# QUTMS-BrakeLight-S00-V01.net
KiCad netlist of a schematic drawn in Altium Designer
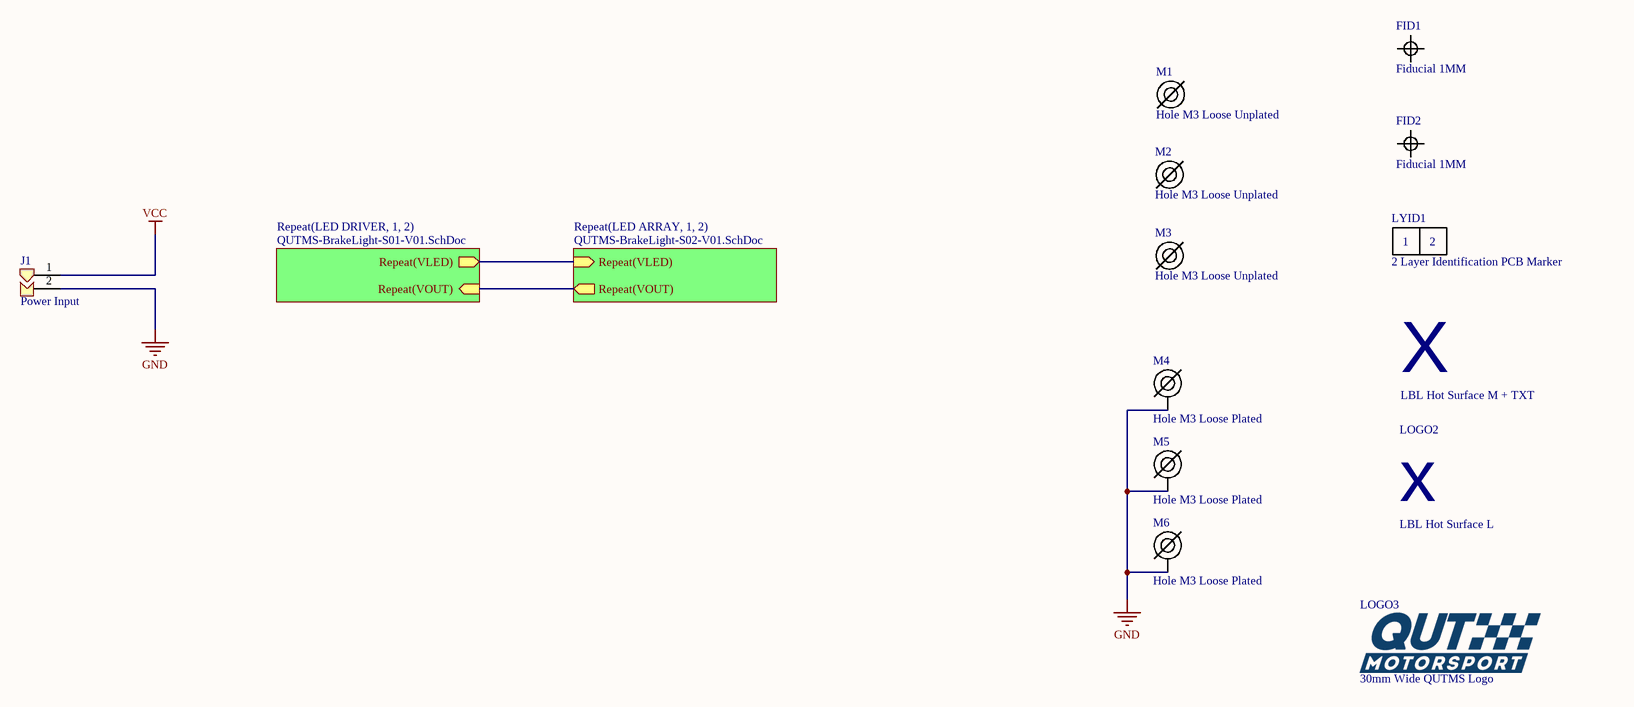
[diagram p0: QUTMS-BrakeLight-S00-V01.SchDoc]

(export (version "E")
  (design (tool "Eeschema 10.0.6"))
  (components
    (comp (ref "FID1")
      (value "Fiducial 1MM")
      (footprint "FIDUCIAL 1MM")
      (libsource (lib "QUTMS_PCBLibrary") (part "Fiducial 1MM"))
    )
    (comp (ref "FID2")
      (value "Fiducial 1MM")
      (footprint "FIDUCIAL 1MM")
      (libsource (lib "QUTMS_PCBLibrary") (part "Fiducial 1MM"))
    )
    (comp (ref "J1")
      (value "Power Input")
      (footprint "Jumper_2Way_Large_Solder_Pad")
      (description "Jumper 2Way Side Large Solderable Pad")
      (libsource (lib "QUTMS_JumperLibrary") (part "Jumper 2Way Side Large Solder Pad"))
    )
    (comp (ref "LOGO1")
      (value "LBL Hot Surface M + TXT")
      (footprint "LBL HOT MEDIUM TXT")
      (libsource (lib "QUTMS_PCBLibrary") (part "LBL Hot Surface M + TXT"))
    )
    (comp (ref "LOGO2")
      (value "LBL Hot Surface L")
      (footprint "LBL HOT LARGE")
      (libsource (lib "QUTMS_PCBLibrary") (part "LBL Hot Surface L"))
    )
    (comp (ref "LOGO3")
      (value "30mm Wide QUTMS Logo")
      (footprint "QUTMS LOGO 30MM")
      (libsource (lib "QUTMS_PCBLibrary") (part "QUTMS Logo 30mm"))
    )
    (comp (ref "LYID1")
      (value "2 Layer Identification PCB Marker")
      (footprint "LAYER IDENT 2")
      (libsource (lib "QUTMS_PCBLibrary") (part "Layer Identification 2"))
    )
    (comp (ref "M1")
      (value "Hole M3 Loose Unplated")
      (footprint "M3.5 UNPLATED")
      (description "M3.5 Hole, No Plating")
      (libsource (lib "QUTMS_PCBLibrary") (part "Hole M3 Loose Unplated"))
    )
    (comp (ref "M2")
      (value "Hole M3 Loose Unplated")
      (footprint "M3.5 UNPLATED")
      (description "M3.5 Hole, No Plating")
      (libsource (lib "QUTMS_PCBLibrary") (part "Hole M3 Loose Unplated"))
    )
    (comp (ref "M3")
      (value "Hole M3 Loose Unplated")
      (footprint "M3.5 UNPLATED")
      (description "M3.5 Hole, No Plating")
      (libsource (lib "QUTMS_PCBLibrary") (part "Hole M3 Loose Unplated"))
    )
    (comp (ref "M4")
      (value "Hole M3 Loose Plated")
      (footprint "M3.5 PLATED")
      (description "M3.5 Hole, Plated")
      (libsource (lib "QUTMS_PCBLibrary") (part "Hole M3 Loose Plated"))
    )
    (comp (ref "M5")
      (value "Hole M3 Loose Plated")
      (footprint "M3.5 PLATED")
      (description "M3.5 Hole, Plated")
      (libsource (lib "QUTMS_PCBLibrary") (part "Hole M3 Loose Plated"))
    )
    (comp (ref "M6")
      (value "Hole M3 Loose Plated")
      (footprint "M3.5 PLATED")
      (description "M3.5 Hole, Plated")
      (libsource (lib "QUTMS_PCBLibrary") (part "Hole M3 Loose Plated"))
    )
  )
  (nets
    (net (code "3") (name "GND") (class "Default")
      (node (ref "J1") (pin "2") (pinfunction "2_2") (pintype "passive"))
      (node (ref "M4") (pin "1") (pinfunction "1_1") (pintype "passive"))
      (node (ref "M5") (pin "1") (pinfunction "1_1") (pintype "passive"))
      (node (ref "M6") (pin "1") (pinfunction "1_1") (pintype "passive"))
    )
    (net (code "4") (name "VCC") (class "Default")
      (node (ref "J1") (pin "1") (pinfunction "1_1") (pintype "passive"))
    )
  )
)
